# Audio_Module.net
KiCad netlist of a schematic drawn in Altium Designer
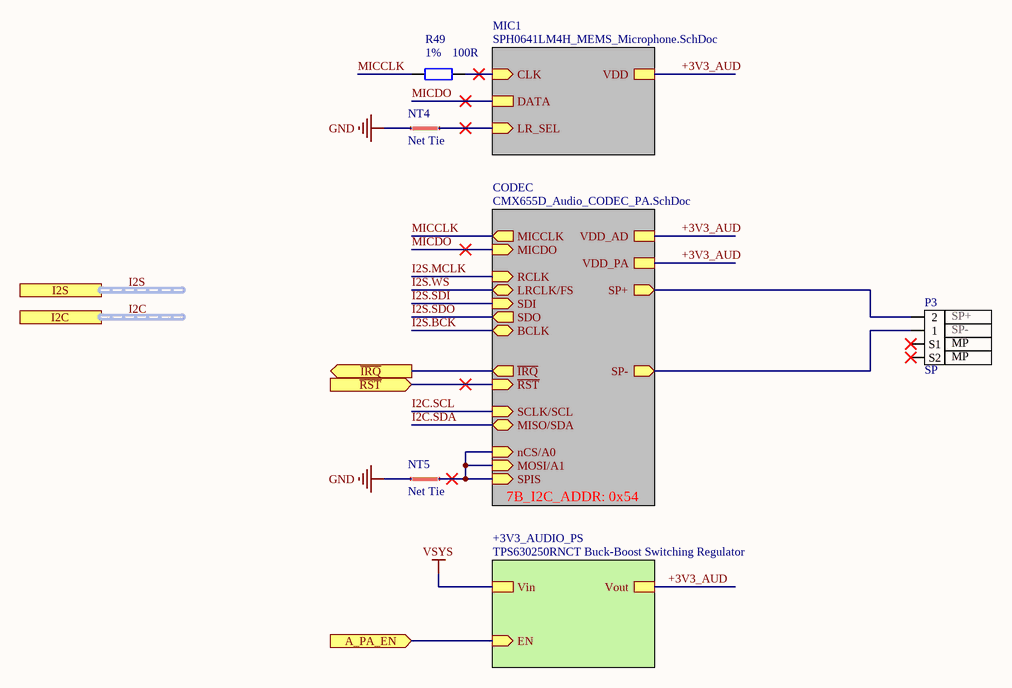
[diagram p0: Audio_Module.SchDoc]

(export (version "E")
  (design (tool "Eeschema 10.0.6"))
  (components
    (comp (ref "NT4")
      (value "Net Tie")
      (footprint "Net Tie 6x30mil")
      (libsource (lib "BLDC_Motor_Driver") (part "Net Tie Line"))
    )
    (comp (ref "NT5")
      (value "Net Tie")
      (footprint "Net Tie 6x30mil")
      (libsource (lib "BLDC_Motor_Driver") (part "Net Tie Line"))
    )
    (comp (ref "P3")
      (value "SP")
      (footprint "CONN_JST_BM2B-SRSS-TB")
      (description "Connector Header Surface Mount 2 position 0.039\" (1.00mm)")
      (fields
        (field (name "MANUFACTURER") "JST")
        (field (name "MANUFACTURER PART NUMBER") "BM02B-SRSS-TB(LF)(SN)")
        (field (name "PIN_1") "SP+")
        (field (name "PIN_2") "SP-")
        (field (name "PIN_MP1") "MP")
        (field (name "PIN_MP2") "MP")
      )
      (libsource (lib "Control_Board_Model") (part "CONN HEADER SMD 2POS 1MM"))
    )
    (comp (ref "R49")
      (value "RES SMD 100 OHM 1% 1/16W 0402")
      (footprint "R0402")
      (description "100 Ohms ±1% 0.063W, 1/16W Chip Resistor 0402 (1005 Metric) Moisture Resistant Thick Film")
      (fields
        (field (name "MANUFACTURER") "Yageo")
        (field (name "MANUFACTURER PART NUMBER") "RC0402FR-07100RL")
        (field (name "TOLERANCE") "1%")
        (field (name "RESISTANCE") "100R")
      )
      (libsource (lib "Control_Board_Model") (part "RES SMD 100 OHM 1% 1/16W 0402"))
    )
  )
  (nets
    (net (code "5") (name "/CLK") (class "Default")
      (node (ref "R49") (pin "1") (pinfunction "1_1") (pintype "passive"))
    )
    (net (code "14") (name "/LR_SEL") (class "Default") (node (ref "NT4") (pin "2") (pintype "passive")))
    (net (code "15") (name "/MICCLK") (class "Default")
      (node (ref "R49") (pin "2") (pinfunction "2_2") (pintype "passive"))
    )
    (net (code "17") (name "/MOSI{slash}A1") (class "Default")
      (node (ref "NT5") (pin "2") (pintype "passive"))
    )
    (net (code "19") (name "/SP+") (class "Default")
      (node (ref "P3") (pin "2") (pinfunction "2_2") (pintype "passive"))
    )
    (net (code "20") (name "/SP-") (class "Default")
      (node (ref "P3") (pin "1") (pinfunction "1_1") (pintype "passive"))
    )
    (net (code "23") (name "GND") (class "Default")
      (node (ref "NT4") (pin "1") (pintype "passive"))
      (node (ref "NT5") (pin "1") (pintype "passive"))
    )
    (net (code "25") (name "unconnected-(P3-PadS1)") (class "Default")
      (node (ref "P3") (pin "S1") (pinfunction "S1_S1") (pintype "passive+no_connect"))
    )
    (net (code "26") (name "unconnected-(P3-PadS2)") (class "Default")
      (node (ref "P3") (pin "S2") (pinfunction "S2_S2") (pintype "passive+no_connect"))
    )
  )
)
